# Accelerometer.net
KiCad netlist of a schematic drawn in Altium Designer
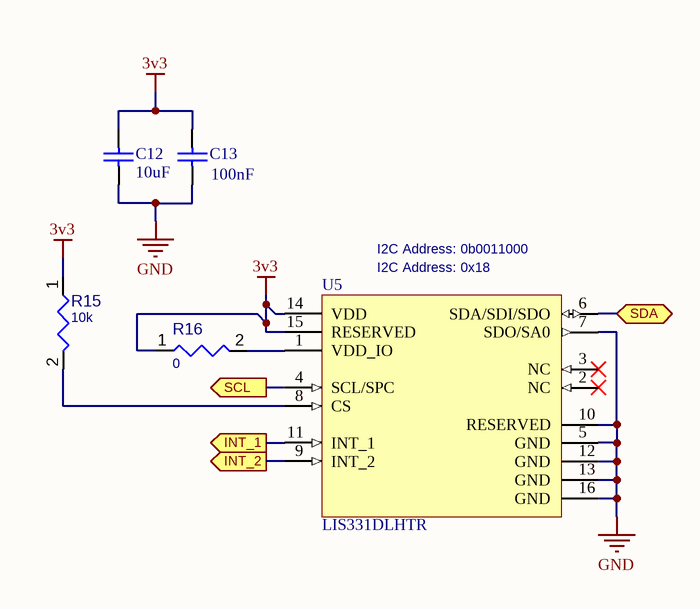
[diagram p0: Accelerometer.SchDoc]

(export (version "E")
  (design (tool "Eeschema 10.0.6"))
  (components
    (comp (ref "C12")
      (value "GRM155R60J106ME44D")
      (footprint "Capacitor_0402")
      (description "CAP CER 10UF 6.3V X5R 0402")
      (fields
        (field (name "CAPACITANCE") "10uF")
        (field (name "TOLERANCE") "20%")
        (field (name "JLCPCB PART #") "C15525")
      )
      (libsource (lib "RIT Launch Initiative") (part "CAPACITOR"))
    )
    (comp (ref "C13")
      (value "GRM155R71E104KE14D")
      (footprint "Capacitor_0402")
      (description "Chip Capacitor 100nF 0402 25V X7R")
      (fields (field (name "CAPACITANCE") "100nF"))
      (libsource (lib "RIT Launch Initiative") (part "CAPACITOR"))
    )
    (comp (ref "R15")
      (value "10k")
      (footprint "RESC0402(1005)_L")
      (description "Chip Resistor, 10 kOhms, +/-1 %, 63 mW, -55 to 125 degC, 0402")
      (fields (field (name "POWER") "63mW") (field (name "TOLERANCE") "1%"))
      (libsource (lib "RIT Launch Initiative") (part "RES-2"))
    )
    (comp (ref "R16")
      (value "0")
      (footprint "RESC0402(1005)_L")
      (description "Jumper 0402")
      (libsource (lib "RIT Launch Initiative") (part "RES-2"))
    )
    (comp (ref "U5")
      (value "LIS331DLHTR")
      (footprint "STM-LGA16-3X3X1")
      (description "LIS331DLH Series 3 Axis ±2/±4/±8 g 3.6V Digital Output Nano Accelerometer LGA-16")
      (libsource (lib "RIT Launch Initiative") (part "SEN-MOT-LIS331DL-16"))
    )
  )
  (nets
    (net (code "1") (name "/INT_1") (class "Default")
      (node (ref "U5") (pin "11") (pinfunction "INT_1_11") (pintype "input"))
    )
    (net (code "2") (name "/INT_2") (class "Default")
      (node (ref "U5") (pin "9") (pinfunction "INT_2_9") (pintype "input"))
    )
    (net (code "3") (name "/SCL") (class "Default")
      (node (ref "U5") (pin "4") (pinfunction "SCL/SPC_4") (pintype "input"))
    )
    (net (code "4") (name "/SDA") (class "Default")
      (node (ref "U5") (pin "6") (pinfunction "SDA/SDI/SDO_6") (pintype "bidirectional"))
    )
    (net (code "5") (name "3v3") (class "Default")
      (node (ref "C12") (pin "2") (pinfunction "2_2") (pintype "passive"))
      (node (ref "C13") (pin "2") (pinfunction "2_2") (pintype "passive"))
      (node (ref "R15") (pin "1") (pinfunction "1_1") (pintype "passive"))
      (node (ref "R16") (pin "1") (pinfunction "1_1") (pintype "passive"))
      (node (ref "U5") (pin "14") (pinfunction "VDD_14") (pintype "power_in"))
      (node (ref "U5") (pin "15") (pinfunction "RESERVED_15") (pintype "power_in"))
    )
    (net (code "6") (name "GND") (class "Default")
      (node (ref "C12") (pin "1") (pinfunction "1_1") (pintype "passive"))
      (node (ref "C13") (pin "1") (pinfunction "1_1") (pintype "passive"))
      (node (ref "U5") (pin "10") (pinfunction "RESERVED_10") (pintype "passive"))
      (node (ref "U5") (pin "12") (pinfunction "GND_12") (pintype "passive"))
      (node (ref "U5") (pin "13") (pinfunction "GND_13") (pintype "passive"))
      (node (ref "U5") (pin "16") (pinfunction "GND_16") (pintype "passive"))
      (node (ref "U5") (pin "5") (pinfunction "GND_5") (pintype "passive"))
      (node (ref "U5") (pin "7") (pinfunction "SDO/SA0_7") (pintype "output"))
    )
    (net (code "7") (name "Net-(U5-CS)") (class "Default")
      (node (ref "R15") (pin "2") (pinfunction "2_2") (pintype "passive"))
      (node (ref "U5") (pin "8") (pinfunction "CS_8") (pintype "input"))
    )
    (net (code "8") (name "Net-(U5-VDD_IO)") (class "Default")
      (node (ref "R16") (pin "2") (pinfunction "2_2") (pintype "passive"))
      (node (ref "U5") (pin "1") (pinfunction "VDD_IO_1") (pintype "power_in"))
    )
    (net (code "9") (name "unconnected-(U5-NC-Pad2)") (class "Default")
      (node (ref "U5") (pin "2") (pinfunction "NC_2") (pintype "input+no_connect"))
    )
    (net (code "10") (name "unconnected-(U5-NC-Pad3)") (class "Default")
      (node (ref "U5") (pin "3") (pinfunction "NC_3") (pintype "input+no_connect"))
    )
  )
)
